# lin_reg_schematic.net
KiCad netlist of a schematic drawn in EAGLE
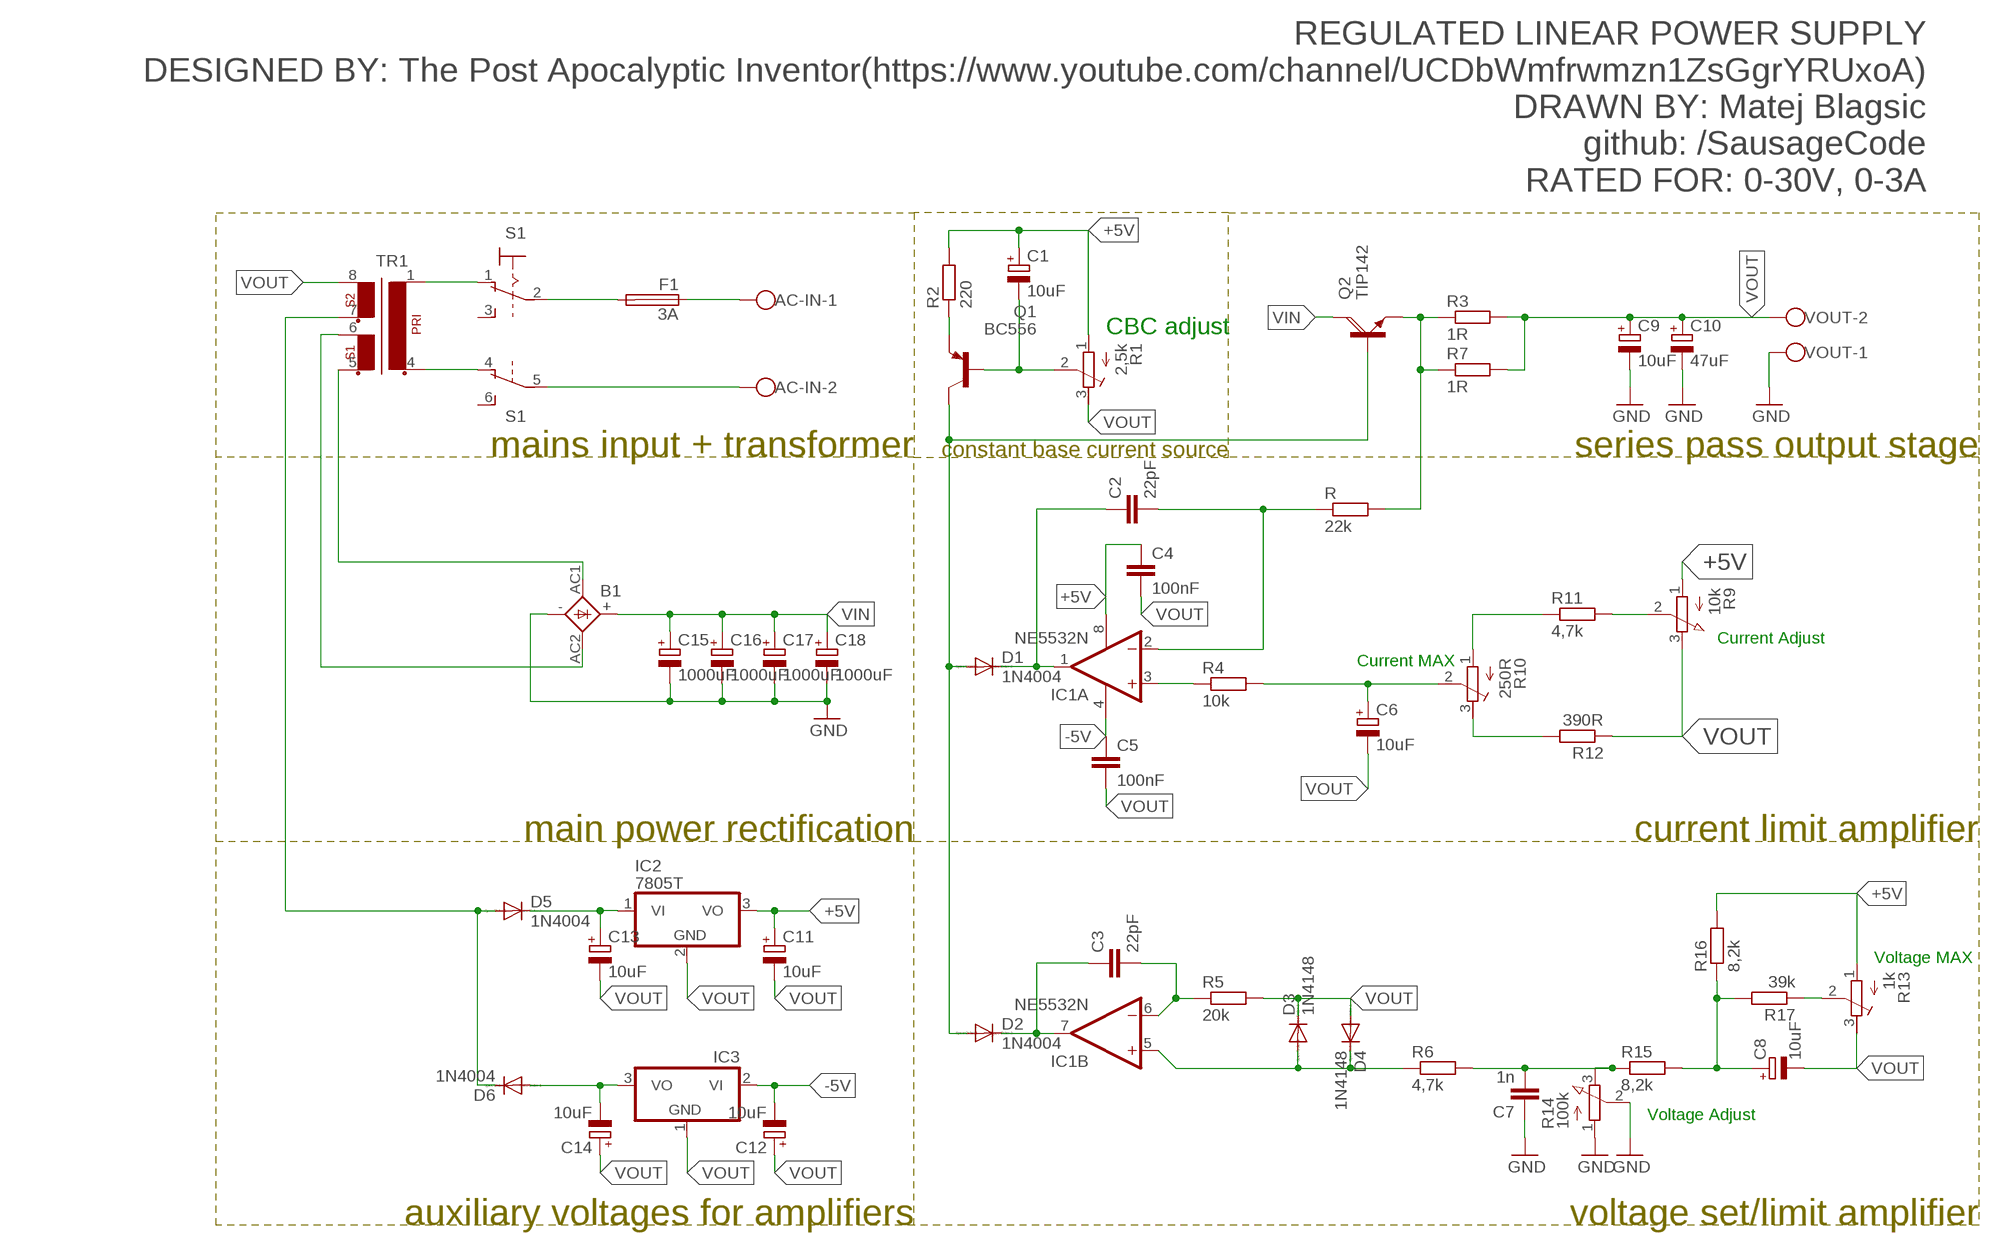
[diagram p0: schematic, sheet 1]

(export (version "E")
  (design (tool "Eeschema 10.0.6"))
  (components
    (comp (ref "AC-IN")
      (value "W237-102")
      (footprint "eagle-import:W237-102")
      (fields (field (name "MPN") "237-102"))
      (libsource (lib "eagle-import") (part "W237-102"))
    )
    (comp (ref "B1")
      (value "2KBB-R")
      (footprint "eagle-import:2KBB-R")
      (libsource (lib "eagle-import") (part "2KBB-R"))
    )
    (comp (ref "C1")
      (value "10uF")
      (footprint "eagle-import:E2-5")
      (libsource (lib "eagle-import") (part "CPOL-EUE2-5"))
    )
    (comp (ref "C2")
      (value "22pF")
      (footprint "eagle-import:C025-025X050")
      (libsource (lib "eagle-import") (part "C-EU025-025X050"))
    )
    (comp (ref "C3")
      (value "22pF")
      (footprint "eagle-import:C025-025X050")
      (libsource (lib "eagle-import") (part "C-EU025-025X050"))
    )
    (comp (ref "C4")
      (value "100nF")
      (footprint "eagle-import:C025-025X050")
      (libsource (lib "eagle-import") (part "C-EU025-025X050"))
    )
    (comp (ref "C5")
      (value "100nF")
      (footprint "eagle-import:C025-025X050")
      (libsource (lib "eagle-import") (part "C-EU025-025X050"))
    )
    (comp (ref "C6")
      (value "10uF")
      (footprint "eagle-import:E2-5")
      (libsource (lib "eagle-import") (part "CPOL-EUE2-5"))
    )
    (comp (ref "C7")
      (value "1n")
      (footprint "eagle-import:C025-025X050")
      (libsource (lib "eagle-import") (part "C-EU025-025X050"))
    )
    (comp (ref "C8")
      (value "10uF")
      (footprint "eagle-import:E2-5")
      (libsource (lib "eagle-import") (part "CPOL-EUE2-5"))
    )
    (comp (ref "C9")
      (value "10uF")
      (footprint "eagle-import:E2-5")
      (libsource (lib "eagle-import") (part "CPOL-EUE2-5"))
    )
    (comp (ref "C10")
      (value "47uF")
      (footprint "eagle-import:E2-5")
      (libsource (lib "eagle-import") (part "CPOL-EUE2-5"))
    )
    (comp (ref "C11")
      (value "10uF")
      (footprint "eagle-import:E2-5")
      (libsource (lib "eagle-import") (part "CPOL-EUE2-5"))
    )
    (comp (ref "C12")
      (value "10uF")
      (footprint "eagle-import:E2-5")
      (libsource (lib "eagle-import") (part "CPOL-EUE2-5"))
    )
    (comp (ref "C13")
      (value "10uF")
      (footprint "eagle-import:E2-5")
      (libsource (lib "eagle-import") (part "CPOL-EUE2-5"))
    )
    (comp (ref "C14")
      (value "10uF")
      (footprint "eagle-import:E2-5")
      (libsource (lib "eagle-import") (part "CPOL-EUE2-5"))
    )
    (comp (ref "C15")
      (value "1000uF")
      (footprint "eagle-import:E2-5")
      (libsource (lib "eagle-import") (part "CPOL-EUE2-5"))
    )
    (comp (ref "C16")
      (value "1000uF")
      (footprint "eagle-import:E2-5")
      (libsource (lib "eagle-import") (part "CPOL-EUE2-5"))
    )
    (comp (ref "C17")
      (value "1000uF")
      (footprint "eagle-import:E2-5")
      (libsource (lib "eagle-import") (part "CPOL-EUE2-5"))
    )
    (comp (ref "C18")
      (value "1000uF")
      (footprint "eagle-import:E2-5")
      (libsource (lib "eagle-import") (part "CPOL-EUE2-5"))
    )
    (comp (ref "D1")
      (value "1N4004")
      (footprint "eagle-import:DO41-10")
      (libsource (lib "eagle-import") (part "1N4004"))
    )
    (comp (ref "D2")
      (value "1N4004")
      (footprint "eagle-import:DO41-10")
      (libsource (lib "eagle-import") (part "1N4004"))
    )
    (comp (ref "D3")
      (value "1N4148")
      (footprint "eagle-import:DO41-10")
      (libsource (lib "eagle-import") (part "1N4004"))
    )
    (comp (ref "D4")
      (value "1N4148")
      (footprint "eagle-import:DO41-10")
      (libsource (lib "eagle-import") (part "1N4004"))
    )
    (comp (ref "D5")
      (value "1N4004")
      (footprint "eagle-import:DO41-10")
      (libsource (lib "eagle-import") (part "1N4004"))
    )
    (comp (ref "D6")
      (value "1N4004")
      (footprint "eagle-import:DO41-10")
      (libsource (lib "eagle-import") (part "1N4004"))
    )
    (comp (ref "F1")
      (value "3A")
      (footprint "eagle-import:GSH15")
      (libsource (lib "eagle-import") (part "FUSEGSH15"))
    )
    (comp (ref "IC1")
      (value "NE5532N")
      (footprint "eagle-import:DIL08")
      (libsource (lib "eagle-import") (part "NE5532N"))
    )
    (comp (ref "IC2")
      (value "7805T")
      (footprint "eagle-import:TO220H")
      (libsource (lib "eagle-import") (part "78T05"))
    )
    (comp (ref "IC3")
      (value "7905T")
      (footprint "eagle-import:TO220H")
      (libsource (lib "eagle-import") (part "79T05"))
    )
    (comp (ref "Q1")
      (value "BC556")
      (footprint "eagle-import:TO92-EBC")
      (libsource (lib "eagle-import") (part "BC556"))
    )
    (comp (ref "Q2")
      (value "TIP142")
      (footprint "eagle-import:SOT93")
      (libsource (lib "eagle-import") (part "TIP142"))
    )
    (comp (ref "R")
      (value "22k")
      (footprint "eagle-import:0207_10")
      (libsource (lib "eagle-import") (part "R-EU_0207/10"))
    )
    (comp (ref "R1")
      (value "2,5k")
      (footprint "eagle-import:RTRIM64W")
      (libsource (lib "eagle-import") (part "R-TRIMM64W"))
    )
    (comp (ref "R2")
      (value "220")
      (footprint "eagle-import:0207_10")
      (libsource (lib "eagle-import") (part "R-EU_0207/10"))
    )
    (comp (ref "R3")
      (value "1R")
      (footprint "eagle-import:0207_10")
      (libsource (lib "eagle-import") (part "R-EU_0207/10"))
    )
    (comp (ref "R4")
      (value "10k")
      (footprint "eagle-import:0207_10")
      (libsource (lib "eagle-import") (part "R-EU_0207/10"))
    )
    (comp (ref "R5")
      (value "20k")
      (footprint "eagle-import:0207_10")
      (libsource (lib "eagle-import") (part "R-EU_0207/10"))
    )
    (comp (ref "R6")
      (value "4,7k")
      (footprint "eagle-import:0207_10")
      (libsource (lib "eagle-import") (part "R-EU_0207/10"))
    )
    (comp (ref "R7")
      (value "1R")
      (footprint "eagle-import:0207_10")
      (libsource (lib "eagle-import") (part "R-EU_0207/10"))
    )
    (comp (ref "R9")
      (value "10k")
      (footprint "eagle-import:3RP_1610N")
      (libsource (lib "eagle-import") (part "3RP/1610N"))
    )
    (comp (ref "R10")
      (value "250R")
      (footprint "eagle-import:RTRIM64W")
      (libsource (lib "eagle-import") (part "R-TRIMM64W"))
    )
    (comp (ref "R11")
      (value "4,7k")
      (footprint "eagle-import:0207_10")
      (libsource (lib "eagle-import") (part "resistor_348_R-EU_0207/10"))
    )
    (comp (ref "R12")
      (value "390R")
      (footprint "eagle-import:0207_10")
      (libsource (lib "eagle-import") (part "resistor_348_R-EU_0207/10"))
    )
    (comp (ref "R13")
      (value "1k")
      (footprint "eagle-import:RTRIM64W")
      (libsource (lib "eagle-import") (part "R-TRIMM64W"))
    )
    (comp (ref "R14")
      (value "100k")
      (footprint "eagle-import:3RP_1610N")
      (libsource (lib "eagle-import") (part "3RP/1610N"))
    )
    (comp (ref "R15")
      (value "8,2k")
      (footprint "eagle-import:0207_10")
      (libsource (lib "eagle-import") (part "R-EU_0207/10"))
    )
    (comp (ref "R16")
      (value "8,2k")
      (footprint "eagle-import:0207_10")
      (libsource (lib "eagle-import") (part "R-EU_0207/10"))
    )
    (comp (ref "R17")
      (value "39k")
      (footprint "eagle-import:0207_10")
      (libsource (lib "eagle-import") (part "R-EU_0207/10"))
    )
    (comp (ref "S1")
      (value "320-938")
      (footprint "eagle-import:320-938")
      (libsource (lib "eagle-import") (part "320-938"))
    )
    (comp (ref "TR1")
      (value "EE20-2")
      (footprint "eagle-import:EE20-2")
      (libsource (lib "eagle-import") (part "EE20-2"))
    )
    (comp (ref "VOUT")
      (value "W237-102")
      (footprint "eagle-import:W237-102")
      (fields (field (name "MPN") "237-102"))
      (libsource (lib "eagle-import") (part "W237-102"))
    )
  )
  (nets
    (net (code "1") (name "+5V") (class "Default")
      (node (ref "C1") (pin "+") (pinfunction "+_+") (pintype "passive"))
      (node (ref "C11") (pin "+") (pinfunction "+_+") (pintype "passive"))
      (node (ref "C4") (pin "1") (pinfunction "1_1") (pintype "passive"))
      (node (ref "IC1") (pin "8") (pinfunction "V+_8") (pintype "power_in"))
      (node (ref "IC2") (pin "3") (pinfunction "VO_3") (pintype "passive"))
      (node (ref "R1") (pin "1") (pinfunction "A_1") (pintype "passive"))
      (node (ref "R13") (pin "1") (pinfunction "A_1") (pintype "passive"))
      (node (ref "R16") (pin "2") (pinfunction "2_2") (pintype "passive"))
      (node (ref "R2") (pin "2") (pinfunction "2_2") (pintype "passive"))
      (node (ref "R9") (pin "1") (pinfunction "A_1") (pintype "passive"))
    )
    (net (code "2") (name "-5V") (class "Default")
      (node (ref "C12") (pin "-") (pinfunction "-_-") (pintype "passive"))
      (node (ref "C5") (pin "1") (pinfunction "1_1") (pintype "passive"))
      (node (ref "IC1") (pin "4") (pinfunction "V-_4") (pintype "power_in"))
      (node (ref "IC3") (pin "2") (pinfunction "VI_2") (pintype "input"))
    )
    (net (code "3") (name "GND") (class "Default")
      (node (ref "B1") (pin "-") (pinfunction "-_-") (pintype "passive"))
      (node (ref "C10") (pin "-") (pinfunction "-_-") (pintype "passive"))
      (node (ref "C15") (pin "-") (pinfunction "-_-") (pintype "passive"))
      (node (ref "C16") (pin "-") (pinfunction "-_-") (pintype "passive"))
      (node (ref "C17") (pin "-") (pinfunction "-_-") (pintype "passive"))
      (node (ref "C18") (pin "-") (pinfunction "-_-") (pintype "passive"))
      (node (ref "C7") (pin "1") (pinfunction "1_1") (pintype "passive"))
      (node (ref "C9") (pin "-") (pinfunction "-_-") (pintype "passive"))
      (node (ref "R14") (pin "1") (pinfunction "A_1") (pintype "passive"))
      (node (ref "R14") (pin "2") (pinfunction "S_2") (pintype "passive"))
      (node (ref "VOUT") (pin "1") (pinfunction "KL_1") (pintype "passive"))
    )
    (net (code "4") (name "Net-(AC-INA-KL)") (class "Default")
      (node (ref "AC-IN") (pin "1") (pinfunction "KL_1") (pintype "passive"))
      (node (ref "F1") (pin "1") (pinfunction "1_1") (pintype "passive"))
    )
    (net (code "5") (name "Net-(AC-INB-KL)") (class "Default")
      (node (ref "AC-IN") (pin "2") (pinfunction "KL_2") (pintype "passive"))
      (node (ref "S1") (pin "5") (pinfunction "P_5") (pintype "passive"))
    )
    (net (code "6") (name "Net-(C8-Pad+)") (class "Default")
      (node (ref "C8") (pin "+") (pinfunction "+_+") (pintype "passive"))
      (node (ref "R15") (pin "2") (pinfunction "2_2") (pintype "passive"))
      (node (ref "R16") (pin "1") (pinfunction "1_1") (pintype "passive"))
      (node (ref "R17") (pin "2") (pinfunction "2_2") (pintype "passive"))
    )
    (net (code "7") (name "Net-(D1-PadA)") (class "Default")
      (node (ref "D1") (pin "A") (pinfunction "A_A") (pintype "passive"))
      (node (ref "D2") (pin "A") (pinfunction "A_A") (pintype "passive"))
      (node (ref "Q1") (pin "C") (pinfunction "C_C") (pintype "passive"))
      (node (ref "Q2") (pin "B") (pinfunction "B_B") (pintype "passive"))
    )
    (net (code "8") (name "Net-(IC1A-+IN)") (class "Default")
      (node (ref "IC1") (pin "3") (pinfunction "+IN_3") (pintype "input"))
      (node (ref "R4") (pin "1") (pinfunction "1_1") (pintype "passive"))
    )
    (net (code "9") (name "Net-(IC1A--IN)") (class "Default")
      (node (ref "C2") (pin "2") (pinfunction "2_2") (pintype "passive"))
      (node (ref "IC1") (pin "2") (pinfunction "-IN_2") (pintype "input"))
      (node (ref "R") (pin "1") (pinfunction "1_1") (pintype "passive"))
    )
    (net (code "10") (name "Net-(IC1A-OUT)") (class "Default")
      (node (ref "C2") (pin "1") (pinfunction "1_1") (pintype "passive"))
      (node (ref "D1") (pin "C") (pinfunction "C_C") (pintype "passive"))
      (node (ref "IC1") (pin "1") (pinfunction "OUT_1") (pintype "output"))
    )
    (net (code "11") (name "Net-(IC1B-+IN)") (class "Default")
      (node (ref "D3") (pin "A") (pinfunction "A_A") (pintype "passive"))
      (node (ref "D4") (pin "C") (pinfunction "C_C") (pintype "passive"))
      (node (ref "IC1") (pin "5") (pinfunction "+IN_5") (pintype "input"))
      (node (ref "R6") (pin "1") (pinfunction "1_1") (pintype "passive"))
    )
    (net (code "12") (name "Net-(IC1B--IN)") (class "Default")
      (node (ref "C3") (pin "2") (pinfunction "2_2") (pintype "passive"))
      (node (ref "IC1") (pin "6") (pinfunction "-IN_6") (pintype "input"))
      (node (ref "R5") (pin "1") (pinfunction "1_1") (pintype "passive"))
    )
    (net (code "13") (name "Net-(IC1B-OUT)") (class "Default")
      (node (ref "C3") (pin "1") (pinfunction "1_1") (pintype "passive"))
      (node (ref "D2") (pin "C") (pinfunction "C_C") (pintype "passive"))
      (node (ref "IC1") (pin "7") (pinfunction "OUT_7") (pintype "output"))
    )
    (net (code "14") (name "Net-(IC2-VI)") (class "Default")
      (node (ref "C13") (pin "+") (pinfunction "+_+") (pintype "passive"))
      (node (ref "D5") (pin "C") (pinfunction "C_C") (pintype "passive"))
      (node (ref "IC2") (pin "1") (pinfunction "VI_1") (pintype "input"))
    )
    (net (code "15") (name "Net-(IC3-VO)") (class "Default")
      (node (ref "C14") (pin "-") (pinfunction "-_-") (pintype "passive"))
      (node (ref "D6") (pin "A") (pinfunction "A_A") (pintype "passive"))
      (node (ref "IC3") (pin "3") (pinfunction "VO_3") (pintype "passive"))
    )
    (net (code "16") (name "Net-(Q1-PadE)") (class "Default")
      (node (ref "Q1") (pin "E") (pinfunction "E_E") (pintype "passive"))
      (node (ref "R2") (pin "1") (pinfunction "1_1") (pintype "passive"))
    )
    (net (code "17") (name "Net-(Q2-PadE)") (class "Default")
      (node (ref "Q2") (pin "E") (pinfunction "E_E") (pintype "passive"))
      (node (ref "R") (pin "2") (pinfunction "2_2") (pintype "passive"))
      (node (ref "R3") (pin "1") (pinfunction "1_1") (pintype "passive"))
      (node (ref "R7") (pin "1") (pinfunction "1_1") (pintype "passive"))
    )
    (net (code "18") (name "Net-(R1-S)") (class "Default")
      (node (ref "C1") (pin "-") (pinfunction "-_-") (pintype "passive"))
      (node (ref "Q1") (pin "B") (pinfunction "B_B") (pintype "passive"))
      (node (ref "R1") (pin "2") (pinfunction "S_2") (pintype "passive"))
    )
    (net (code "19") (name "Net-(R9-S)") (class "Default")
      (node (ref "R11") (pin "2") (pinfunction "2_2") (pintype "passive"))
      (node (ref "R9") (pin "2") (pinfunction "S_2") (pintype "passive"))
    )
    (net (code "20") (name "Net-(R10-A)") (class "Default")
      (node (ref "R10") (pin "1") (pinfunction "A_1") (pintype "passive"))
      (node (ref "R11") (pin "1") (pinfunction "1_1") (pintype "passive"))
    )
    (net (code "21") (name "Net-(R10-E)") (class "Default")
      (node (ref "R10") (pin "3") (pinfunction "E_3") (pintype "passive"))
      (node (ref "R12") (pin "2") (pinfunction "2_2") (pintype "passive"))
    )
    (net (code "22") (name "Net-(R10-S)") (class "Default")
      (node (ref "C6") (pin "+") (pinfunction "+_+") (pintype "passive"))
      (node (ref "R10") (pin "2") (pinfunction "S_2") (pintype "passive"))
      (node (ref "R4") (pin "2") (pinfunction "2_2") (pintype "passive"))
    )
    (net (code "23") (name "Net-(R13-S)") (class "Default")
      (node (ref "R13") (pin "2") (pinfunction "S_2") (pintype "passive"))
      (node (ref "R17") (pin "1") (pinfunction "1_1") (pintype "passive"))
    )
    (net (code "24") (name "Net-(R14-E)") (class "Default")
      (node (ref "C7") (pin "2") (pinfunction "2_2") (pintype "passive"))
      (node (ref "R14") (pin "3") (pinfunction "E_3") (pintype "passive"))
      (node (ref "R15") (pin "1") (pinfunction "1_1") (pintype "passive"))
      (node (ref "R6") (pin "2") (pinfunction "2_2") (pintype "passive"))
    )
    (net (code "25") (name "Net-(S1A-O)") (class "Default")
      (node (ref "S1") (pin "1") (pinfunction "O_1") (pintype "passive"))
      (node (ref "TR1") (pin "1") (pinfunction "1_1") (pintype "passive"))
    )
    (net (code "26") (name "Net-(S1A-P)") (class "Default")
      (node (ref "F1") (pin "2") (pinfunction "2_2") (pintype "passive"))
      (node (ref "S1") (pin "2") (pinfunction "P_2") (pintype "passive"))
    )
    (net (code "27") (name "Net-(S1B-O)") (class "Default")
      (node (ref "S1") (pin "4") (pinfunction "O_4") (pintype "passive"))
      (node (ref "TR1") (pin "4") (pinfunction "2_4") (pintype "passive"))
    )
    (net (code "28") (name "Net-(TR1-3)") (class "Default")
      (node (ref "B1") (pin "AC1") (pinfunction "AC1_AC1") (pintype "passive"))
      (node (ref "TR1") (pin "5") (pinfunction "3_5") (pintype "passive"))
    )
    (net (code "29") (name "Net-(TR1-4)") (class "Default")
      (node (ref "B1") (pin "AC2") (pinfunction "AC2_AC2") (pintype "passive"))
      (node (ref "TR1") (pin "6") (pinfunction "4_6") (pintype "passive"))
    )
    (net (code "30") (name "Net-(TR1-5)") (class "Default")
      (node (ref "D5") (pin "A") (pinfunction "A_A") (pintype "passive"))
      (node (ref "D6") (pin "C") (pinfunction "C_C") (pintype "passive"))
      (node (ref "TR1") (pin "7") (pinfunction "5_7") (pintype "passive"))
    )
    (net (code "31") (name "VIN") (class "Default")
      (node (ref "B1") (pin "+") (pinfunction "+_+") (pintype "passive"))
      (node (ref "C15") (pin "+") (pinfunction "+_+") (pintype "passive"))
      (node (ref "C16") (pin "+") (pinfunction "+_+") (pintype "passive"))
      (node (ref "C17") (pin "+") (pinfunction "+_+") (pintype "passive"))
      (node (ref "C18") (pin "+") (pinfunction "+_+") (pintype "passive"))
      (node (ref "Q2") (pin "C") (pinfunction "C_C") (pintype "passive"))
    )
    (net (code "32") (name "VOUT") (class "Default")
      (node (ref "C10") (pin "+") (pinfunction "+_+") (pintype "passive"))
      (node (ref "C11") (pin "-") (pinfunction "-_-") (pintype "passive"))
      (node (ref "C12") (pin "+") (pinfunction "+_+") (pintype "passive"))
      (node (ref "C13") (pin "-") (pinfunction "-_-") (pintype "passive"))
      (node (ref "C14") (pin "+") (pinfunction "+_+") (pintype "passive"))
      (node (ref "C4") (pin "2") (pinfunction "2_2") (pintype "passive"))
      (node (ref "C5") (pin "2") (pinfunction "2_2") (pintype "passive"))
      (node (ref "C6") (pin "-") (pinfunction "-_-") (pintype "passive"))
      (node (ref "C8") (pin "-") (pinfunction "-_-") (pintype "passive"))
      (node (ref "C9") (pin "+") (pinfunction "+_+") (pintype "passive"))
      (node (ref "D3") (pin "C") (pinfunction "C_C") (pintype "passive"))
      (node (ref "D4") (pin "A") (pinfunction "A_A") (pintype "passive"))
      (node (ref "IC2") (pin "2") (pinfunction "GND_2") (pintype "passive"))
      (node (ref "IC3") (pin "1") (pinfunction "GND_1") (pintype "passive"))
      (node (ref "R1") (pin "3") (pinfunction "E_3") (pintype "passive"))
      (node (ref "R12") (pin "1") (pinfunction "1_1") (pintype "passive"))
      (node (ref "R13") (pin "3") (pinfunction "E_3") (pintype "passive"))
      (node (ref "R3") (pin "2") (pinfunction "2_2") (pintype "passive"))
      (node (ref "R5") (pin "2") (pinfunction "2_2") (pintype "passive"))
      (node (ref "R7") (pin "2") (pinfunction "2_2") (pintype "passive"))
      (node (ref "R9") (pin "3") (pinfunction "E_3") (pintype "passive"))
      (node (ref "TR1") (pin "8") (pinfunction "6_8") (pintype "passive"))
      (node (ref "VOUT") (pin "2") (pinfunction "KL_2") (pintype "passive"))
    )
    (net (code "33") (name "unconnected-(S1A-S-Pad3)") (class "Default")
      (node (ref "S1") (pin "3") (pinfunction "S_3") (pintype "passive"))
    )
    (net (code "34") (name "unconnected-(S1B-S-Pad6)") (class "Default")
      (node (ref "S1") (pin "6") (pinfunction "S_6") (pintype "passive"))
    )
  )
)
